# 01_-_Shaper_Stages.net
KiCad netlist of a schematic drawn in Altium Designer
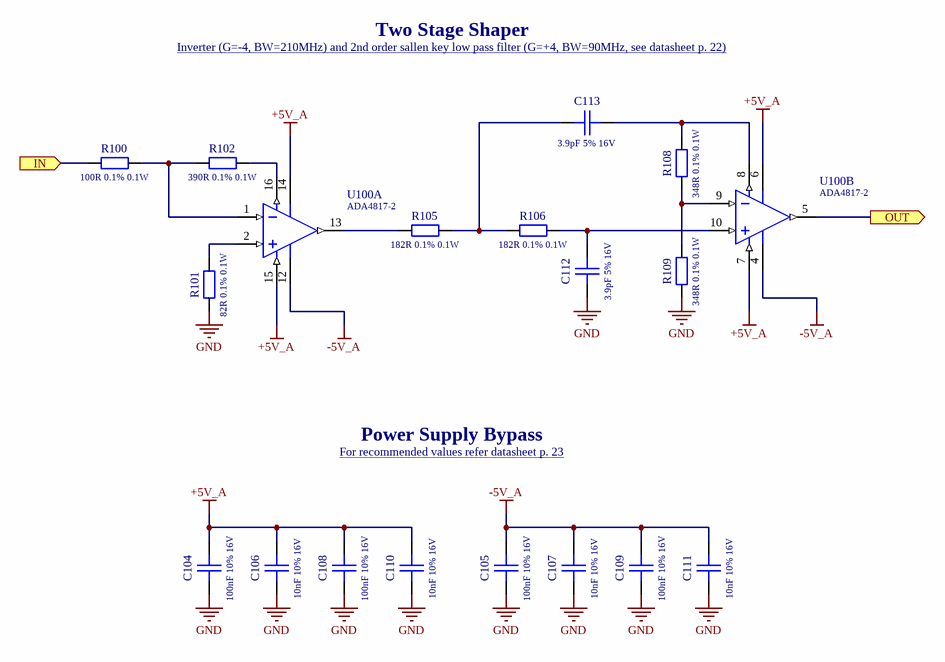
[diagram p0: [01] - Shaper Stages.SchDoc]

(export (version "E")
  (design (tool "Eeschema 10.0.6"))
  (components
    (comp (ref "C104")
      (value "100nF 10% 16V")
      (footprint "0603_CAP")
      (description "Simple generic capacitor.")
      (libsource (lib "CustomComponents") (part "Capacitor"))
    )
    (comp (ref "C105")
      (value "100nF 10% 16V")
      (footprint "0603_CAP")
      (description "Simple generic capacitor.")
      (libsource (lib "CustomComponents") (part "Capacitor"))
    )
    (comp (ref "C106")
      (value "10nF 10% 16V")
      (footprint "0603_CAP")
      (description "Simple generic capacitor.")
      (libsource (lib "CustomComponents") (part "Capacitor"))
    )
    (comp (ref "C107")
      (value "10nF 10% 16V")
      (footprint "0603_CAP")
      (description "Simple generic capacitor.")
      (libsource (lib "CustomComponents") (part "Capacitor"))
    )
    (comp (ref "C108")
      (value "100nF 10% 16V")
      (footprint "0603_CAP")
      (description "Simple generic capacitor.")
      (libsource (lib "CustomComponents") (part "Capacitor"))
    )
    (comp (ref "C109")
      (value "100nF 10% 16V")
      (footprint "0603_CAP")
      (description "Simple generic capacitor.")
      (libsource (lib "CustomComponents") (part "Capacitor"))
    )
    (comp (ref "C110")
      (value "10nF 10% 16V")
      (footprint "0603_CAP")
      (description "Simple generic capacitor.")
      (libsource (lib "CustomComponents") (part "Capacitor"))
    )
    (comp (ref "C111")
      (value "10nF 10% 16V")
      (footprint "0603_CAP")
      (description "Simple generic capacitor.")
      (libsource (lib "CustomComponents") (part "Capacitor"))
    )
    (comp (ref "C112")
      (value "3.9pF 5% 16V")
      (footprint "0603_CAP")
      (description "Simple generic capacitor.")
      (libsource (lib "CustomComponents") (part "Capacitor"))
    )
    (comp (ref "C113")
      (value "3.9pF 5% 16V")
      (footprint "0603_CAP")
      (description "Simple generic capacitor.")
      (libsource (lib "CustomComponents") (part "Capacitor"))
    )
    (comp (ref "R100")
      (value "100R 0.1% 0.1W")
      (footprint "0603_RES")
      (description "Simple generic resistor.")
      (libsource (lib "CustomComponents") (part "Resistor"))
    )
    (comp (ref "R101")
      (value "82R 0.1% 0.1W")
      (footprint "0603_RES")
      (description "Simple generic resistor.")
      (libsource (lib "CustomComponents") (part "Resistor"))
    )
    (comp (ref "R102")
      (value "390R 0.1% 0.1W")
      (footprint "0603_RES")
      (description "Simple generic resistor.")
      (libsource (lib "CustomComponents") (part "Resistor"))
    )
    (comp (ref "R105")
      (value "182R 0.1% 0.1W")
      (footprint "0603_RES")
      (description "Simple generic resistor.")
      (libsource (lib "CustomComponents") (part "Resistor"))
    )
    (comp (ref "R106")
      (value "182R 0.1% 0.1W")
      (footprint "0603_RES")
      (description "Simple generic resistor.")
      (libsource (lib "CustomComponents") (part "Resistor"))
    )
    (comp (ref "R108")
      (value "348R 0.1% 0.1W")
      (footprint "0603_RES")
      (description "Simple generic resistor.")
      (libsource (lib "CustomComponents") (part "Resistor"))
    )
    (comp (ref "R109")
      (value "348R 0.1% 0.1W")
      (footprint "0603_RES")
      (description "Simple generic resistor.")
      (libsource (lib "CustomComponents") (part "Resistor"))
    )
    (comp (ref "U100")
      (value "ADA4817-2")
      (footprint "LFCSP-16")
      (description "Low Noise, 1 GHz FastFET Op Amps")
      (fields (field (name "MANUFACTURER") "Analog Devices") (field (name "PARTNUMBER") "LMV358QDGKR"))
      (libsource (lib "CustomComponents") (part "ADA4817-2"))
    )
  )
  (nets
    (net (code "1") (name "+5V_A") (class "Default")
      (node (ref "C104") (pin "2") (pinfunction "2_2") (pintype "passive"))
      (node (ref "C106") (pin "2") (pinfunction "2_2") (pintype "passive"))
      (node (ref "C108") (pin "2") (pinfunction "2_2") (pintype "passive"))
      (node (ref "C110") (pin "2") (pinfunction "2_2") (pintype "passive"))
      (node (ref "U100") (pin "14") (pinfunction "VS+_14") (pintype "power_in"))
      (node (ref "U100") (pin "15") (pinfunction "~{PD}_15") (pintype "input"))
      (node (ref "U100") (pin "6") (pinfunction "#VS2_6") (pintype "power_in"))
      (node (ref "U100") (pin "7") (pinfunction "~{PD2}_7") (pintype "input"))
    )
    (net (code "2") (name "-5V_A") (class "Default")
      (node (ref "C105") (pin "2") (pinfunction "2_2") (pintype "passive"))
      (node (ref "C107") (pin "2") (pinfunction "2_2") (pintype "passive"))
      (node (ref "C109") (pin "2") (pinfunction "2_2") (pintype "passive"))
      (node (ref "C111") (pin "2") (pinfunction "2_2") (pintype "passive"))
      (node (ref "U100") (pin "12") (pinfunction "-VS1_12") (pintype "power_in"))
      (node (ref "U100") (pin "4") (pinfunction "-VS2_4") (pintype "power_in"))
    )
    (net (code "3") (name "/IN") (class "Default")
      (node (ref "R100") (pin "2") (pinfunction "2_2") (pintype "passive"))
    )
    (net (code "4") (name "/OUT") (class "Default")
      (node (ref "U100") (pin "5") (pinfunction "OUT2_5") (pintype "output"))
    )
    (net (code "5") (name "GND") (class "Default")
      (node (ref "C104") (pin "1") (pinfunction "1_1") (pintype "passive"))
      (node (ref "C105") (pin "1") (pinfunction "1_1") (pintype "passive"))
      (node (ref "C106") (pin "1") (pinfunction "1_1") (pintype "passive"))
      (node (ref "C107") (pin "1") (pinfunction "1_1") (pintype "passive"))
      (node (ref "C108") (pin "1") (pinfunction "1_1") (pintype "passive"))
      (node (ref "C109") (pin "1") (pinfunction "1_1") (pintype "passive"))
      (node (ref "C110") (pin "1") (pinfunction "1_1") (pintype "passive"))
      (node (ref "C111") (pin "1") (pinfunction "1_1") (pintype "passive"))
      (node (ref "C112") (pin "1") (pinfunction "1_1") (pintype "passive"))
      (node (ref "R101") (pin "2") (pinfunction "2_2") (pintype "passive"))
      (node (ref "R109") (pin "2") (pinfunction "2_2") (pintype "passive"))
    )
    (net (code "6") (name "Net-(C113-Pad1)") (class "Default")
      (node (ref "C113") (pin "1") (pinfunction "1_1") (pintype "passive"))
      (node (ref "R105") (pin "1") (pinfunction "1_1") (pintype "passive"))
      (node (ref "R106") (pin "2") (pinfunction "2_2") (pintype "passive"))
    )
    (net (code "7") (name "Net-(U100A-FB1)") (class "Default")
      (node (ref "R102") (pin "1") (pinfunction "1_1") (pintype "passive"))
      (node (ref "U100") (pin "16") (pinfunction "FB1_16") (pintype "output"))
    )
    (net (code "8") (name "Net-(U100A-IN1-)") (class "Default")
      (node (ref "R100") (pin "1") (pinfunction "1_1") (pintype "passive"))
      (node (ref "R102") (pin "2") (pinfunction "2_2") (pintype "passive"))
      (node (ref "U100") (pin "1") (pinfunction "IN1-_1") (pintype "input"))
    )
    (net (code "9") (name "Net-(U100A-IN2+)") (class "Default")
      (node (ref "R101") (pin "1") (pinfunction "1_1") (pintype "passive"))
      (node (ref "U100") (pin "2") (pinfunction "IN2+_2") (pintype "input"))
    )
    (net (code "10") (name "Net-(U100A-OUT1)") (class "Default")
      (node (ref "R105") (pin "2") (pinfunction "2_2") (pintype "passive"))
      (node (ref "U100") (pin "13") (pinfunction "OUT1_13") (pintype "output"))
    )
    (net (code "11") (name "Net-(U100B-FB2)") (class "Default")
      (node (ref "C113") (pin "2") (pinfunction "2_2") (pintype "passive"))
      (node (ref "R108") (pin "1") (pinfunction "1_1") (pintype "passive"))
      (node (ref "U100") (pin "8") (pinfunction "FB2_8") (pintype "output"))
    )
    (net (code "12") (name "Net-(U100B-IN2+)") (class "Default")
      (node (ref "C112") (pin "2") (pinfunction "2_2") (pintype "passive"))
      (node (ref "R106") (pin "1") (pinfunction "1_1") (pintype "passive"))
      (node (ref "U100") (pin "10") (pinfunction "IN2+_10") (pintype "input"))
    )
    (net (code "13") (name "Net-(U100B-IN2-)") (class "Default")
      (node (ref "R108") (pin "2") (pinfunction "2_2") (pintype "passive"))
      (node (ref "R109") (pin "1") (pinfunction "1_1") (pintype "passive"))
      (node (ref "U100") (pin "9") (pinfunction "IN2-_9") (pintype "input"))
    )
  )
)
